# SPI.net
KiCad netlist of a schematic drawn in Altium Designer
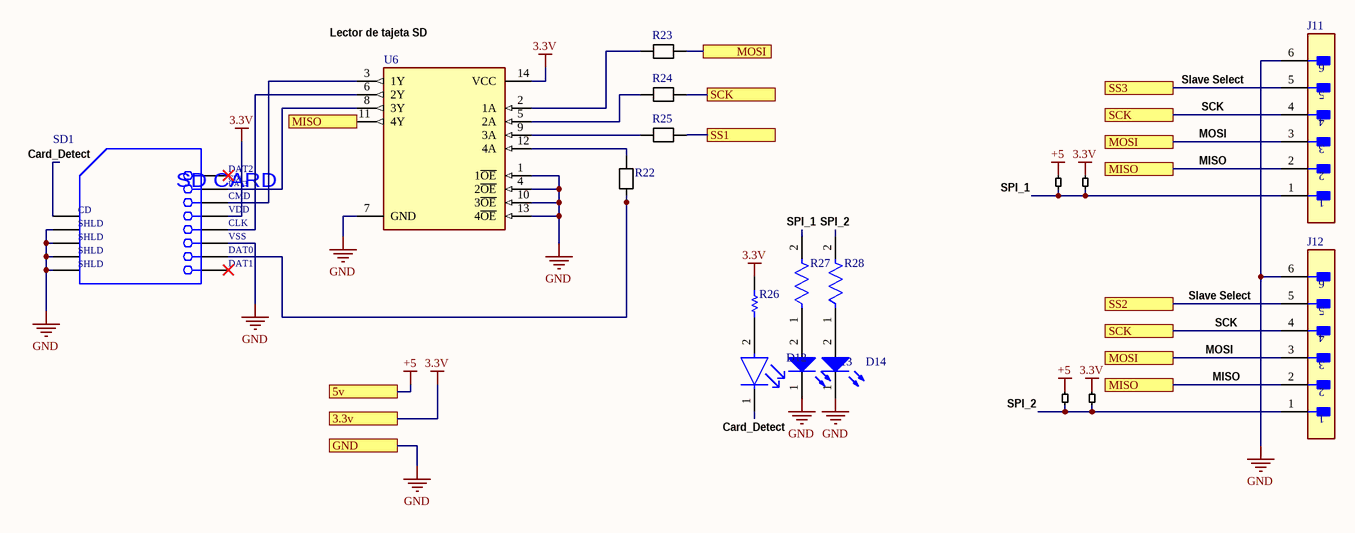
[diagram p0: SPI.SchDoc]

(export (version "E")
  (design (tool "Eeschema 10.0.6"))
  (components
    (comp (ref "D12")
      (value "LTST-C170KFKT")
      (footprint "FP-LTST-C170KFKT-MFG")
      (description "LED ORANGE CLEAR SMD")
      (libsource (lib "Altium Content Vault") (part "8706943c75ba83719d021d2fdc84c58"))
    )
    (comp (ref "D13")
      (value "150080BS75000")
      (footprint "WL-SMCW_0805_150080xx75000")
      (libsource (lib "Altium Content Vault") (part "LED_Blue_2A-1K"))
    )
    (comp (ref "D14")
      (value "150080BS75000")
      (footprint "WL-SMCW_0805_150080xx75000")
      (libsource (lib "Altium Content Vault") (part "LED_Blue_2A-1K"))
    )
    (comp (ref "J11")
      (value "B6B-XH-A(LF)(SN)")
      (footprint "FP-B6B-XH-A_LF_SN-MFG")
      (description "CONN HEADER VERT 6POS 2.5MM")
      (libsource (lib "Altium Content Vault") (part "f2cb566baf1c37ab5a3b8e90bbeafd6"))
    )
    (comp (ref "J12")
      (value "B6B-XH-A(LF)(SN)")
      (footprint "FP-B6B-XH-A_LF_SN-MFG")
      (description "CONN HEADER VERT 6POS 2.5MM")
      (libsource (lib "Altium Content Vault") (part "f2cb566baf1c37ab5a3b8e90bbeafd6"))
    )
    (comp (ref "R22")
      (value "3k3")
      (footprint "1206")
      (fields (field (name "MP") "RGC1206DTC10K0"))
      (libsource (lib "RGC1206DTC10K0") (part "RGC1206DTC10K0"))
    )
    (comp (ref "R23")
      (value "3k3")
      (footprint "1206")
      (fields (field (name "MP") "RGC1206DTC10K0"))
      (libsource (lib "RGC1206DTC10K0") (part "RGC1206DTC10K0"))
    )
    (comp (ref "R24")
      (value "3k3")
      (footprint "1206")
      (fields (field (name "MP") "RGC1206DTC10K0"))
      (libsource (lib "RGC1206DTC10K0") (part "RGC1206DTC10K0"))
    )
    (comp (ref "R25")
      (value "3k3")
      (footprint "1206")
      (fields (field (name "MP") "RGC1206DTC10K0"))
      (libsource (lib "RGC1206DTC10K0") (part "RGC1206DTC10K0"))
    )
    (comp (ref "R26")
      (value "ERJ6ENF6800V")
      (footprint "RESC2013X70X40ML20T20")
      (fields (field (name "MANUFACTURER") "Panasonic"))
      (libsource (lib "Altium Content Vault") (part "RES"))
    )
    (comp (ref "R27")
      (value "ERJ-P06F1001V")
      (footprint "FP-ERJP06-MFG")
      (description "RES SMD 1K OHM 1% 1/2W 0805")
      (fields (field (name "TOLERANCE") "1%"))
      (libsource (lib "Altium Content Vault") (part "1029c3af85768c4190bb7ad29bc67b5"))
    )
    (comp (ref "R28")
      (value "ERJ-P06F1001V")
      (footprint "FP-ERJP06-MFG")
      (description "RES SMD 1K OHM 1% 1/2W 0805")
      (fields (field (name "TOLERANCE") "1%"))
      (libsource (lib "Altium Content Vault") (part "1029c3af85768c4190bb7ad29bc67b5"))
    )
    (comp (ref "SD1")
      (value "473521001")
      (footprint "MOLX-473521001_V")
      (description "MicroSD(TM), Pitch 1.1 mm, 8 Position, Height 1.88 mm, -20 to 85 degC, RoHS, Tape and Reel")
      (fields (field (name "MANUFACTURER") "Molex"))
      (libsource (lib "Altium Content Vault") (part "CN-SD-8-1SW-4S"))
    )
    (comp (ref "U6")
      (value "SN74LVC125APWR")
      (footprint "FP-PW0014A-IPC_B")
      (description "IC BUF NON-INVERT 3.6V 14TSSOP")
      (libsource (lib "Altium Content Vault") (part "0c185306b27c65c3e4a0d950f37c68a"))
    )
    (comp (ref "W21") (value "Jumper") (footprint "Jumper Mid") (libsource (lib "Schlib1") (part "Jumper")))
    (comp (ref "W22") (value "Jumper") (footprint "Jumper Mid") (libsource (lib "Schlib1") (part "Jumper")))
    (comp (ref "W23") (value "Jumper") (footprint "Jumper Mid") (libsource (lib "Schlib1") (part "Jumper")))
    (comp (ref "W24") (value "Jumper") (footprint "Jumper Mid") (libsource (lib "Schlib1") (part "Jumper")))
  )
  (nets
    (net (code "1") (name "+5") (class "Default")
      (node (ref "W21") (pin "2") (pinfunction "2_2") (pintype "passive"))
      (node (ref "W22") (pin "2") (pinfunction "2_2") (pintype "passive"))
    )
    (net (code "2") (name "/Card_Detect") (class "Default")
      (node (ref "D12") (pin "1") (pinfunction "C_1") (pintype "passive"))
      (node (ref "SD1") (pin "9") (pinfunction "CD_9") (pintype "passive"))
    )
    (net (code "3") (name "/MISO") (class "Default")
      (node (ref "J11") (pin "2") (pinfunction "2_2") (pintype "passive"))
      (node (ref "J12") (pin "2") (pinfunction "2_2") (pintype "passive"))
      (node (ref "U6") (pin "11") (pinfunction "4Y_11") (pintype "output"))
    )
    (net (code "4") (name "/MOSI") (class "Default")
      (node (ref "J11") (pin "3") (pinfunction "3_3") (pintype "passive"))
      (node (ref "J12") (pin "3") (pinfunction "3_3") (pintype "passive"))
      (node (ref "R23") (pin "2") (pinfunction "2_2") (pintype "passive"))
    )
    (net (code "5") (name "/SCK") (class "Default")
      (node (ref "J11") (pin "4") (pinfunction "4_4") (pintype "passive"))
      (node (ref "J12") (pin "4") (pinfunction "4_4") (pintype "passive"))
      (node (ref "R24") (pin "2") (pinfunction "2_2") (pintype "passive"))
    )
    (net (code "6") (name "/SPI_1") (class "Default")
      (node (ref "J11") (pin "1") (pinfunction "1_1") (pintype "passive"))
      (node (ref "R27") (pin "2") (pinfunction "2_2") (pintype "passive"))
      (node (ref "W21") (pin "1") (pinfunction "1_1") (pintype "passive"))
      (node (ref "W23") (pin "1") (pinfunction "1_1") (pintype "passive"))
    )
    (net (code "7") (name "/SPI_2") (class "Default")
      (node (ref "J12") (pin "1") (pinfunction "1_1") (pintype "passive"))
      (node (ref "R28") (pin "2") (pinfunction "2_2") (pintype "passive"))
      (node (ref "W22") (pin "1") (pinfunction "1_1") (pintype "passive"))
      (node (ref "W24") (pin "1") (pinfunction "1_1") (pintype "passive"))
    )
    (net (code "8") (name "/SS1") (class "Default")
      (node (ref "R25") (pin "2") (pinfunction "2_2") (pintype "passive"))
    )
    (net (code "9") (name "/SS2") (class "Default")
      (node (ref "J12") (pin "5") (pinfunction "5_5") (pintype "passive"))
    )
    (net (code "10") (name "/SS3") (class "Default")
      (node (ref "J11") (pin "5") (pinfunction "5_5") (pintype "passive"))
    )
    (net (code "11") (name "3.3V") (class "Default")
      (node (ref "R26") (pin "2") (pinfunction "2_2") (pintype "passive"))
      (node (ref "SD1") (pin "4") (pinfunction "VDD_4") (pintype "passive"))
      (node (ref "U6") (pin "14") (pinfunction "VCC_14") (pintype "power_in"))
      (node (ref "W23") (pin "2") (pinfunction "2_2") (pintype "passive"))
      (node (ref "W24") (pin "2") (pinfunction "2_2") (pintype "passive"))
    )
    (net (code "12") (name "GND") (class "Default")
      (node (ref "D13") (pin "1") (pinfunction "K_1") (pintype "passive"))
      (node (ref "D14") (pin "1") (pinfunction "K_1") (pintype "passive"))
      (node (ref "J11") (pin "6") (pinfunction "6_6") (pintype "passive"))
      (node (ref "J12") (pin "6") (pinfunction "6_6") (pintype "passive"))
      (node (ref "SD1") (pin "10") (pinfunction "SHLD_10") (pintype "passive"))
      (node (ref "SD1") (pin "11") (pinfunction "SHLD_11") (pintype "passive"))
      (node (ref "SD1") (pin "12") (pinfunction "SHLD_12") (pintype "passive"))
      (node (ref "SD1") (pin "13") (pinfunction "SHLD_13") (pintype "passive"))
      (node (ref "SD1") (pin "6") (pinfunction "VSS_6") (pintype "passive"))
      (node (ref "U6") (pin "1") (pinfunction "1~{OE}_1") (pintype "input"))
      (node (ref "U6") (pin "10") (pinfunction "3~{OE}_10") (pintype "input"))
      (node (ref "U6") (pin "13") (pinfunction "4~{OE}_13") (pintype "input"))
      (node (ref "U6") (pin "4") (pinfunction "2~{OE}_4") (pintype "input"))
      (node (ref "U6") (pin "7") (pinfunction "GND_7") (pintype "power_in"))
    )
    (net (code "13") (name "Net-(D12-A)") (class "Default")
      (node (ref "D12") (pin "2") (pinfunction "A_2") (pintype "passive"))
      (node (ref "R26") (pin "1") (pinfunction "1_1") (pintype "passive"))
    )
    (net (code "14") (name "Net-(D13-A)") (class "Default")
      (node (ref "D13") (pin "2") (pinfunction "A_2") (pintype "passive"))
      (node (ref "R27") (pin "1") (pinfunction "1_1") (pintype "passive"))
    )
    (net (code "15") (name "Net-(D14-A)") (class "Default")
      (node (ref "D14") (pin "2") (pinfunction "A_2") (pintype "passive"))
      (node (ref "R28") (pin "1") (pinfunction "1_1") (pintype "passive"))
    )
    (net (code "16") (name "Net-(SD1-CD{slash}DAT3)") (class "Default")
      (node (ref "SD1") (pin "2") (pinfunction "CD/DAT3_2") (pintype "passive"))
      (node (ref "U6") (pin "8") (pinfunction "3Y_8") (pintype "output"))
    )
    (net (code "17") (name "Net-(SD1-CLK)") (class "Default")
      (node (ref "SD1") (pin "5") (pinfunction "CLK_5") (pintype "passive"))
      (node (ref "U6") (pin "6") (pinfunction "2Y_6") (pintype "output"))
    )
    (net (code "18") (name "Net-(SD1-CMD)") (class "Default")
      (node (ref "SD1") (pin "3") (pinfunction "CMD_3") (pintype "passive"))
      (node (ref "U6") (pin "3") (pinfunction "1Y_3") (pintype "output"))
    )
    (net (code "19") (name "Net-(SD1-DAT0)") (class "Default")
      (node (ref "R22") (pin "2") (pinfunction "2_2") (pintype "passive"))
      (node (ref "SD1") (pin "7") (pinfunction "DAT0_7") (pintype "passive"))
    )
    (net (code "20") (name "Net-(U6-1A)") (class "Default")
      (node (ref "R23") (pin "1") (pinfunction "1_1") (pintype "passive"))
      (node (ref "U6") (pin "2") (pinfunction "1A_2") (pintype "input"))
    )
    (net (code "21") (name "Net-(U6-2A)") (class "Default")
      (node (ref "R24") (pin "1") (pinfunction "1_1") (pintype "passive"))
      (node (ref "U6") (pin "5") (pinfunction "2A_5") (pintype "input"))
    )
    (net (code "22") (name "Net-(U6-3A)") (class "Default")
      (node (ref "R25") (pin "1") (pinfunction "1_1") (pintype "passive"))
      (node (ref "U6") (pin "9") (pinfunction "3A_9") (pintype "input"))
    )
    (net (code "23") (name "Net-(U6-4A)") (class "Default")
      (node (ref "R22") (pin "1") (pinfunction "1_1") (pintype "passive"))
      (node (ref "U6") (pin "12") (pinfunction "4A_12") (pintype "input"))
    )
    (net (code "24") (name "unconnected-(SD1-DAT1-Pad8)") (class "Default")
      (node (ref "SD1") (pin "8") (pinfunction "DAT1_8") (pintype "passive+no_connect"))
    )
    (net (code "25") (name "unconnected-(SD1-DAT2-Pad1)") (class "Default")
      (node (ref "SD1") (pin "1") (pinfunction "DAT2_1") (pintype "passive+no_connect"))
    )
  )
)
